# OUTPUT.net
KiCad netlist of a schematic drawn in Altium Designer
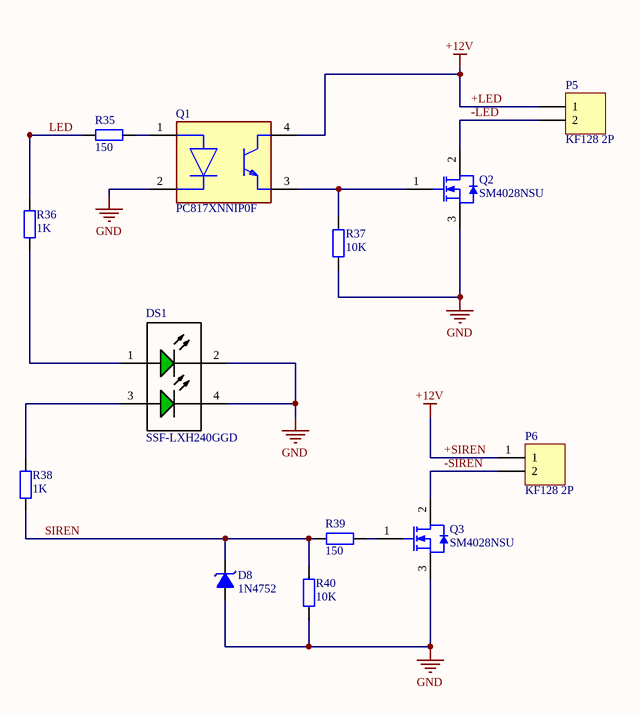
[diagram p0: OUTPUT.SchDoc]

(export (version "E")
  (design (tool "Eeschema 10.0.6"))
  (components
    (comp (ref "D8")
      (value "1N4752")
      (footprint "DIODE ZENNER SMD SOD80")
      (description "Dán")
      (libsource (lib "Approxi") (part "Diode Zener 15V"))
    )
    (comp (ref "DS1")
      (value "SSF-LXH240GGD")
      (footprint "LUMX-SSF-LXH240GGD_V")
      (description "LED, Green, 105 mW, 2.2 V, -40 to 85 degC, 4-Pin THD, RoHD, Bulk")
      (fields (field (name "MANUFACTURER") "Lumex"))
      (libsource (lib "Altium Content Vault") (part "LED-GREEN-AKAK-4"))
    )
    (comp (ref "P5")
      (value "KF128 2P")
      (footprint "KF128_2P")
      (description "Header, 2-Pin, pitch 5.08mm")
      (fields (field (name "MPN") "KF128-2P"))
      (libsource (lib "") (part "KF128 2P_1"))
    )
    (comp (ref "P6")
      (value "KF128 2P")
      (footprint "KF128_2P")
      (description "Header, 2-Pin, pitch 5.08mm")
      (fields (field (name "MPN") "KF128-2P"))
      (libsource (lib "Integrated_Library_gateway_tbl") (part "KF128 2P"))
    )
    (comp (ref "Q1")
      (value "PC817XNNIP0F")
      (footprint "FP-PC817XNNIP0F-MFG")
      (description "OPTOISOLATOR 5KV TRANS 4SMD")
      (libsource (lib "Approxi") (part "6470904bf6395c62928ee73e60120b8"))
    )
    (comp (ref "Q2")
      (value "SM4028NSU")
      (footprint "INF-PG-TO252-3-313_L")
      (fields (field (name "MANUFACTURER") "Infineon") (field (name "PARTNUMBER") "IPD60R600C6"))
      (libsource (lib "Approxi") (part "INF-NEMOS-GDS-3"))
    )
    (comp (ref "Q3")
      (value "SM4028NSU")
      (footprint "INF-PG-TO252-3-313_L")
      (fields (field (name "MANUFACTURER") "Infineon") (field (name "PARTNUMBER") "IPD60R600C6"))
      (libsource (lib "Approxi") (part "INF-NEMOS-GDS-3"))
    )
    (comp (ref "R35")
      (value "150")
      (footprint "tro smd 0805")
      (description "Dán")
      (libsource (lib "Approxi") (part "Tro 0603 5% 10k"))
    )
    (comp (ref "R36")
      (value "1K")
      (footprint "tro smd 0805")
      (description "Dán")
      (libsource (lib "Approxi") (part "Tro 0603 5% 10k"))
    )
    (comp (ref "R37")
      (value "10K")
      (footprint "tro smd 0805")
      (description "Dán")
      (libsource (lib "Approxi") (part "Tro 0603 5% 10k"))
    )
    (comp (ref "R38")
      (value "1K")
      (footprint "tro smd 0805")
      (description "Dán")
      (libsource (lib "Approxi") (part "Tro 0603 5% 10k"))
    )
    (comp (ref "R39")
      (value "150")
      (footprint "tro smd 0805")
      (description "Dán")
      (libsource (lib "Approxi") (part "Tro 0603 5% 10k"))
    )
    (comp (ref "R40")
      (value "10K")
      (footprint "tro smd 0805")
      (description "Dán")
      (libsource (lib "Approxi") (part "Tro 0603 5% 10k"))
    )
  )
  (nets
    (net (code "1") (name "+12V") (class "Default")
      (node (ref "P5") (pin "1") (pinfunction "1_1") (pintype "passive"))
      (node (ref "P6") (pin "1") (pinfunction "1_1") (pintype "passive"))
      (node (ref "Q1") (pin "4") (pinfunction "C_4") (pintype "passive"))
    )
    (net (code "2") (name "/-LED") (class "Default")
      (node (ref "P5") (pin "2") (pinfunction "2_2") (pintype "passive"))
      (node (ref "Q2") (pin "2") (pinfunction "DRAIN_2") (pintype "passive"))
    )
    (net (code "3") (name "/-SIREN") (class "Default")
      (node (ref "P6") (pin "2") (pinfunction "2_2") (pintype "passive"))
      (node (ref "Q3") (pin "2") (pinfunction "DRAIN_2") (pintype "passive"))
    )
    (net (code "4") (name "/LED") (class "Default")
      (node (ref "R35") (pin "2") (pinfunction "2_2") (pintype "passive"))
      (node (ref "R36") (pin "2") (pinfunction "2_2") (pintype "passive"))
    )
    (net (code "5") (name "/SIREN") (class "Default")
      (node (ref "D8") (pin "2") (pinfunction "K_2") (pintype "passive"))
      (node (ref "R38") (pin "1") (pinfunction "1_1") (pintype "passive"))
      (node (ref "R39") (pin "2") (pinfunction "2_2") (pintype "passive"))
      (node (ref "R40") (pin "1") (pinfunction "1_1") (pintype "passive"))
    )
    (net (code "6") (name "GND") (class "Default")
      (node (ref "D8") (pin "1") (pinfunction "A_1") (pintype "passive"))
      (node (ref "DS1") (pin "2") (pinfunction "K_2") (pintype "passive"))
      (node (ref "DS1") (pin "4") (pinfunction "K_4") (pintype "passive"))
      (node (ref "Q1") (pin "2") (pinfunction "C_2") (pintype "passive"))
      (node (ref "Q2") (pin "3") (pinfunction "SOURCE_3") (pintype "passive"))
      (node (ref "Q3") (pin "3") (pinfunction "SOURCE_3") (pintype "passive"))
      (node (ref "R37") (pin "2") (pinfunction "2_2") (pintype "passive"))
      (node (ref "R40") (pin "2") (pinfunction "2_2") (pintype "passive"))
    )
    (net (code "7") (name "Net-(DS1-A-Pad1)") (class "Default")
      (node (ref "DS1") (pin "1") (pinfunction "A_1") (pintype "passive"))
      (node (ref "R36") (pin "1") (pinfunction "1_1") (pintype "passive"))
    )
    (net (code "8") (name "Net-(DS1-A-Pad3)") (class "Default")
      (node (ref "DS1") (pin "3") (pinfunction "A_3") (pintype "passive"))
      (node (ref "R38") (pin "2") (pinfunction "2_2") (pintype "passive"))
    )
    (net (code "9") (name "Net-(Q1-A)") (class "Default")
      (node (ref "Q1") (pin "1") (pinfunction "A_1") (pintype "passive"))
      (node (ref "R35") (pin "1") (pinfunction "1_1") (pintype "passive"))
    )
    (net (code "10") (name "Net-(Q1-E)") (class "Default")
      (node (ref "Q1") (pin "3") (pinfunction "E_3") (pintype "passive"))
      (node (ref "Q2") (pin "1") (pinfunction "GATE_1") (pintype "passive"))
      (node (ref "R37") (pin "1") (pinfunction "1_1") (pintype "passive"))
    )
    (net (code "11") (name "Net-(Q3-GATE)") (class "Default")
      (node (ref "Q3") (pin "1") (pinfunction "GATE_1") (pintype "passive"))
      (node (ref "R39") (pin "1") (pinfunction "1_1") (pintype "passive"))
    )
  )
)
